# mcu.net
KiCad netlist of a schematic drawn in Altium Designer
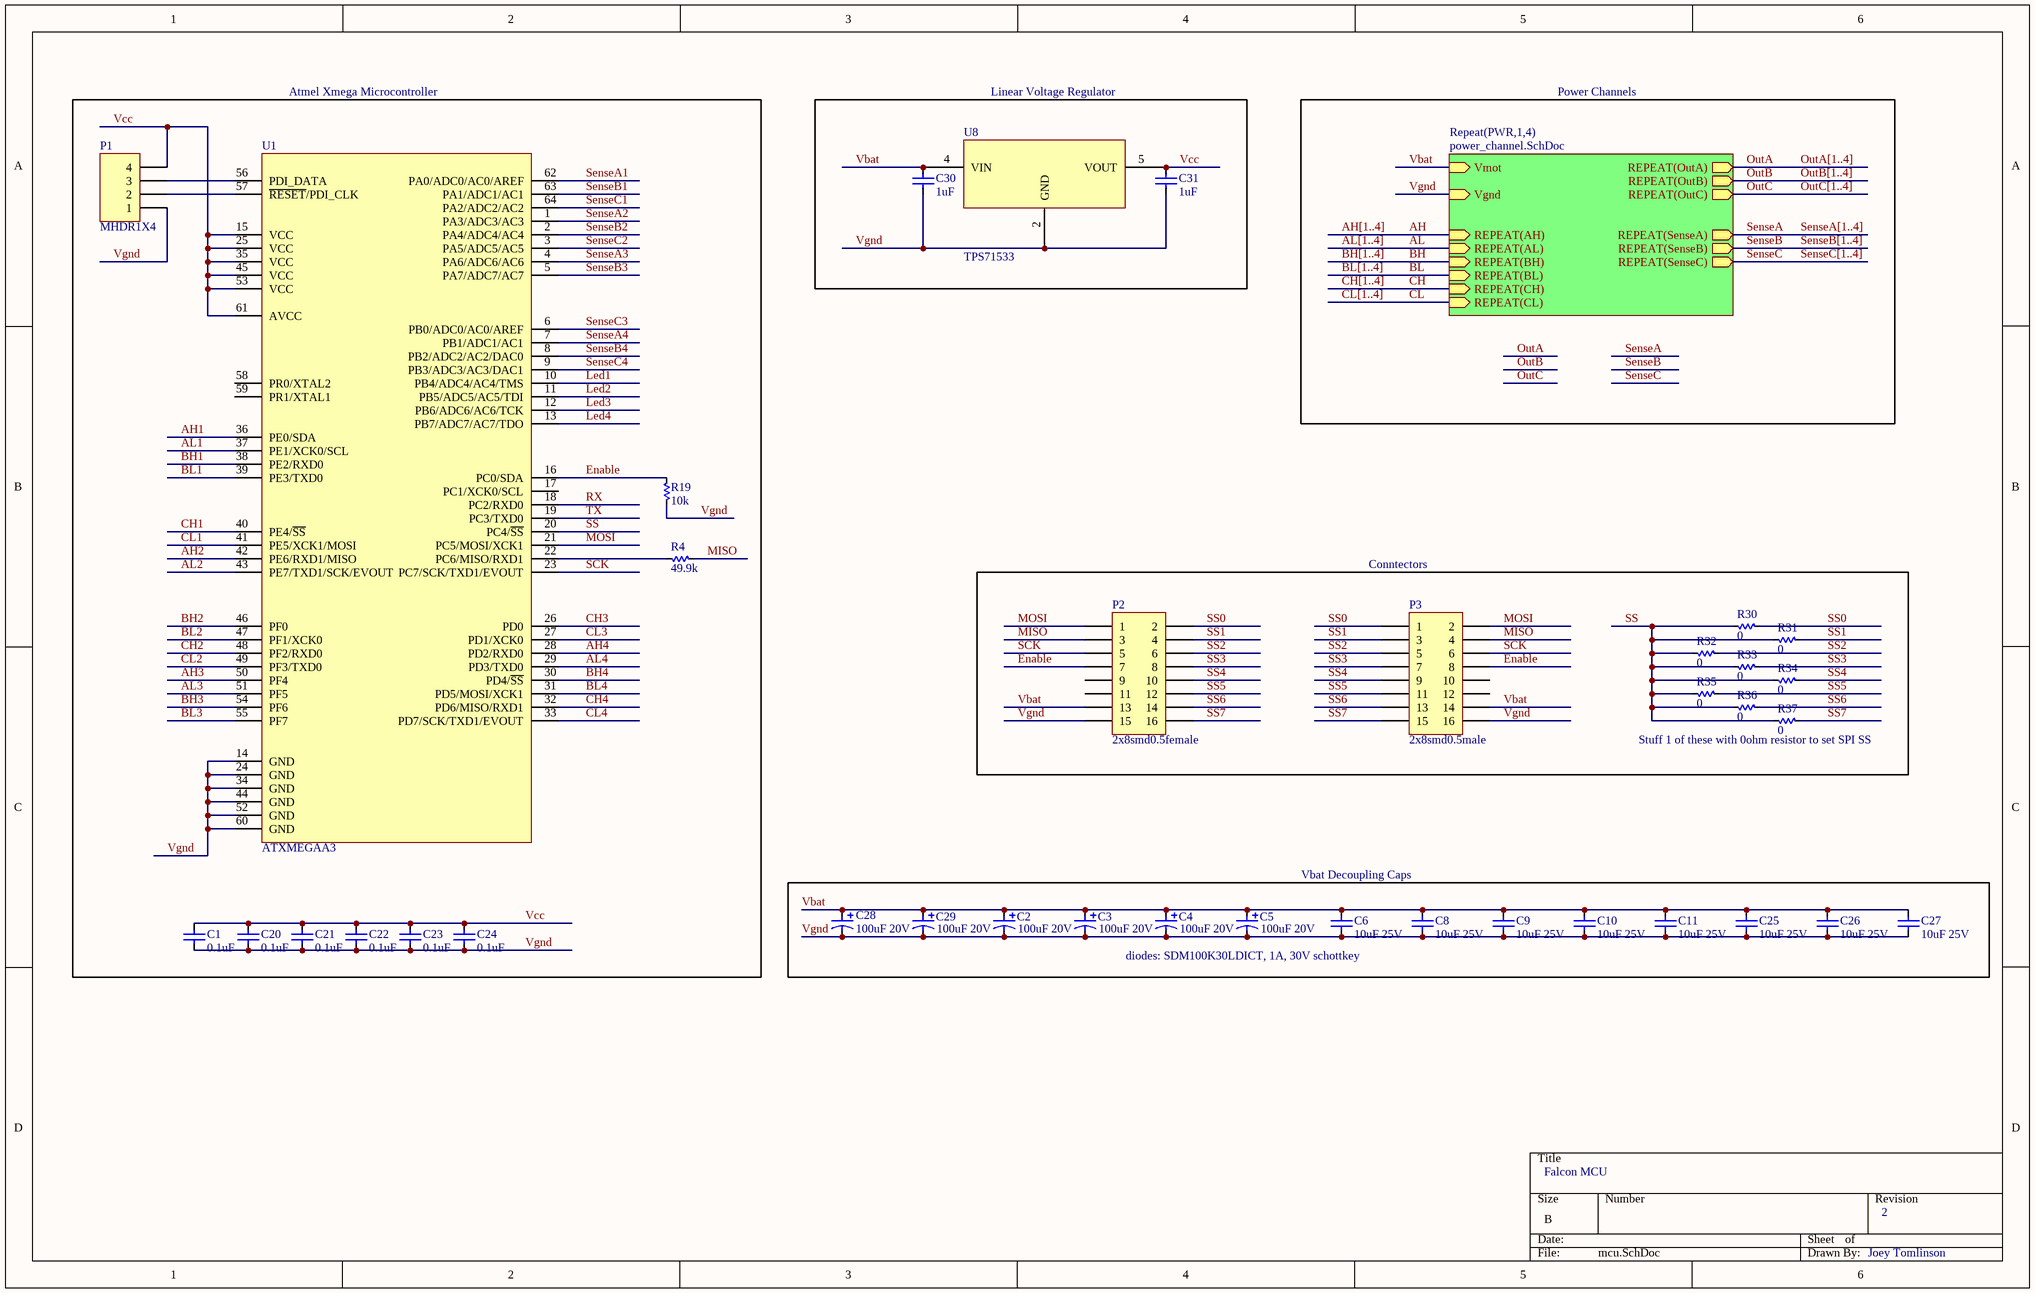
[diagram p0: mcu.SchDoc]

(export (version "E")
  (design (tool "Eeschema 10.0.6"))
  (components
    (comp (ref "C1")
      (value "0.1uF")
      (footprint "0603 (1608)")
      (fields (field (name "PART NO.") "490-1524-1-ND") (field (name "Comment") "Capacitor"))
      (libsource (lib "SMT Chip") (part "Capacitor"))
    )
    (comp (ref "C2")
      (value "100uF 20V")
      (footprint "7343 (TANT E)")
      (fields (field (name "PART NO.") "718-1370-1-ND") (field (name "Comment") "Polarized Capacitor"))
      (libsource (lib "SMT Chip") (part "Polarized Capacitor"))
    )
    (comp (ref "C3")
      (value "100uF 20V")
      (footprint "7343 (TANT E)")
      (fields (field (name "PART NO.") "718-1370-1-ND") (field (name "Comment") "Polarized Capacitor"))
      (libsource (lib "SMT Chip") (part "Polarized Capacitor"))
    )
    (comp (ref "C4")
      (value "100uF 20V")
      (footprint "7343 (TANT E)")
      (fields (field (name "PART NO.") "718-1370-1-ND") (field (name "Comment") "Polarized Capacitor"))
      (libsource (lib "SMT Chip") (part "Polarized Capacitor"))
    )
    (comp (ref "C5")
      (value "100uF 20V")
      (footprint "7343 (TANT E)")
      (fields (field (name "PART NO.") "718-1370-1-ND") (field (name "Comment") "Polarized Capacitor"))
      (libsource (lib "SMT Chip") (part "Polarized Capacitor"))
    )
    (comp (ref "C6")
      (value "10uF 25V")
      (footprint "0805 (2012)")
      (fields (field (name "PART NO.") "490-5523-1-ND") (field (name "Comment") "Capacitor"))
      (libsource (lib "SMT Chip") (part "Capacitor"))
    )
    (comp (ref "C8")
      (value "10uF 25V")
      (footprint "0805 (2012)")
      (fields (field (name "PART NO.") "490-5523-1-ND") (field (name "Comment") "Capacitor"))
      (libsource (lib "SMT Chip") (part "Capacitor"))
    )
    (comp (ref "C9")
      (value "10uF 25V")
      (footprint "0805 (2012)")
      (fields (field (name "PART NO.") "490-5523-1-ND") (field (name "Comment") "Capacitor"))
      (libsource (lib "SMT Chip") (part "Capacitor"))
    )
    (comp (ref "C10")
      (value "10uF 25V")
      (footprint "0805 (2012)")
      (fields (field (name "PART NO.") "490-5523-1-ND") (field (name "Comment") "Capacitor"))
      (libsource (lib "SMT Chip") (part "Capacitor"))
    )
    (comp (ref "C11")
      (value "10uF 25V")
      (footprint "0805 (2012)")
      (fields (field (name "PART NO.") "490-5523-1-ND") (field (name "Comment") "Capacitor"))
      (libsource (lib "SMT Chip") (part "Capacitor"))
    )
    (comp (ref "C20")
      (value "0.1uF")
      (footprint "0603 (1608)")
      (fields (field (name "PART NO.") "490-1524-1-ND") (field (name "Comment") "Capacitor"))
      (libsource (lib "SMT Chip") (part "Capacitor"))
    )
    (comp (ref "C21")
      (value "0.1uF")
      (footprint "0603 (1608)")
      (fields (field (name "PART NO.") "490-1524-1-ND") (field (name "Comment") "Capacitor"))
      (libsource (lib "SMT Chip") (part "Capacitor"))
    )
    (comp (ref "C22")
      (value "0.1uF")
      (footprint "0603 (1608)")
      (fields (field (name "PART NO.") "490-1524-1-ND") (field (name "Comment") "Capacitor"))
      (libsource (lib "SMT Chip") (part "Capacitor"))
    )
    (comp (ref "C23")
      (value "0.1uF")
      (footprint "0603 (1608)")
      (fields (field (name "PART NO.") "490-1524-1-ND") (field (name "Comment") "Capacitor"))
      (libsource (lib "SMT Chip") (part "Capacitor"))
    )
    (comp (ref "C24")
      (value "0.1uF")
      (footprint "0603 (1608)")
      (fields (field (name "PART NO.") "490-1524-1-ND") (field (name "Comment") "Capacitor"))
      (libsource (lib "SMT Chip") (part "Capacitor"))
    )
    (comp (ref "C25")
      (value "10uF 25V")
      (footprint "0805 (2012)")
      (fields (field (name "PART NO.") "490-5523-1-ND") (field (name "Comment") "Capacitor"))
      (libsource (lib "SMT Chip") (part "Capacitor"))
    )
    (comp (ref "C26")
      (value "10uF 25V")
      (footprint "0805 (2012)")
      (fields (field (name "PART NO.") "490-5523-1-ND") (field (name "Comment") "Capacitor"))
      (libsource (lib "SMT Chip") (part "Capacitor"))
    )
    (comp (ref "C27")
      (value "10uF 25V")
      (footprint "0805 (2012)")
      (fields (field (name "PART NO.") "490-5523-1-ND") (field (name "Comment") "Capacitor"))
      (libsource (lib "SMT Chip") (part "Capacitor"))
    )
    (comp (ref "C28")
      (value "100uF 20V")
      (footprint "7343 (TANT E)")
      (fields (field (name "PART NO.") "718-1370-1-ND") (field (name "Comment") "Polarized Capacitor"))
      (libsource (lib "SMT Chip") (part "Polarized Capacitor"))
    )
    (comp (ref "C29")
      (value "100uF 20V")
      (footprint "7343 (TANT E)")
      (fields (field (name "PART NO.") "718-1370-1-ND") (field (name "Comment") "Polarized Capacitor"))
      (libsource (lib "SMT Chip") (part "Polarized Capacitor"))
    )
    (comp (ref "C30")
      (value "1uF")
      (footprint "0603 (1608)")
      (fields (field (name "PART NO.") "445-3452-1-ND") (field (name "Comment") "Capacitor"))
      (libsource (lib "SMT Chip") (part "Capacitor"))
    )
    (comp (ref "C31")
      (value "1uF")
      (footprint "0603 (1608)")
      (fields (field (name "PART NO.") "445-3452-1-ND") (field (name "Comment") "Capacitor"))
      (libsource (lib "SMT Chip") (part "Capacitor"))
    )
    (comp (ref "P1")
      (value "MHDR1X4")
      (footprint "MHDR1X4")
      (description "Header, 4-Pin")
      (fields (field (name "PART NO.") "Not Stuffed") (field (name "PUBLISHER") "Altium Limited"))
      (libsource (lib "Miscellaneous Connectors") (part "MHDR1X4"))
    )
    (comp (ref "P2")
      (value "2x8smd0.5female")
      (footprint "S9007E-08-ND")
      (fields (field (name "PART NO.") "S9007E-08-ND"))
      (libsource (lib "falcon") (part "2x8smd0.5female"))
    )
    (comp (ref "P3")
      (value "2x8smd0.5male")
      (footprint "S9007E-08-ND")
      (fields (field (name "PART NO.") "S9013E-08-ND"))
      (libsource (lib "falcon") (part "2x8smd0.5male"))
    )
    (comp (ref "R4")
      (value "49.9k")
      (footprint "0603 (1608)")
      (description "Resistor")
      (fields (field (name "PART NO.") "P49.9HCT-ND"))
      (libsource (lib "SMT Chip") (part "Resistor"))
    )
    (comp (ref "R19")
      (value "10k")
      (footprint "0603 (1608)")
      (description "Resistor")
      (fields (field (name "PART NO.") "RMCF0603JT10K0CT-ND"))
      (libsource (lib "SMT Chip") (part "Resistor"))
    )
    (comp (ref "R30")
      (value "0")
      (footprint "0603 (1608)")
      (description "Resistor")
      (fields (field (name "PART NO.") "RMCF0603ZT0R00CT-ND"))
      (libsource (lib "SMT Chip") (part "Resistor"))
    )
    (comp (ref "R31")
      (value "0")
      (footprint "0603 (1608)")
      (description "Resistor")
      (fields (field (name "PART NO.") "RMCF0603ZT0R00CT-ND"))
      (libsource (lib "SMT Chip") (part "Resistor"))
    )
    (comp (ref "R32")
      (value "0")
      (footprint "0603 (1608)")
      (description "Resistor")
      (fields (field (name "PART NO.") "RMCF0603ZT0R00CT-ND"))
      (libsource (lib "SMT Chip") (part "Resistor"))
    )
    (comp (ref "R33")
      (value "0")
      (footprint "0603 (1608)")
      (description "Resistor")
      (fields (field (name "PART NO.") "RMCF0603ZT0R00CT-ND"))
      (libsource (lib "SMT Chip") (part "Resistor"))
    )
    (comp (ref "R34")
      (value "0")
      (footprint "0603 (1608)")
      (description "Resistor")
      (fields (field (name "PART NO.") "RMCF0603ZT0R00CT-ND"))
      (libsource (lib "SMT Chip") (part "Resistor"))
    )
    (comp (ref "R35")
      (value "0")
      (footprint "0603 (1608)")
      (description "Resistor")
      (fields (field (name "PART NO.") "RMCF0603ZT0R00CT-ND"))
      (libsource (lib "SMT Chip") (part "Resistor"))
    )
    (comp (ref "R36")
      (value "0")
      (footprint "0603 (1608)")
      (description "Resistor")
      (fields (field (name "PART NO.") "RMCF0603ZT0R00CT-ND"))
      (libsource (lib "SMT Chip") (part "Resistor"))
    )
    (comp (ref "R37")
      (value "0")
      (footprint "0603 (1608)")
      (description "Resistor")
      (fields (field (name "PART NO.") "RMCF0603ZT0R00CT-ND"))
      (libsource (lib "SMT Chip") (part "Resistor"))
    )
    (comp (ref "U1")
      (value "ATXMEGAA3")
      (footprint "QFN-64")
      (fields (field (name "MANUFACTURER") "Atmel") (field (name "PART NO.") "ATXMEGA128A3-MH-ND"))
      (libsource (lib "XMEGA") (part "ATXMEGAA3"))
    )
    (comp (ref "U8")
      (value "TPS71533")
      (footprint "SOT23-5")
      (fields (field (name "PART NO.") "296-12008-1-ND"))
      (libsource (lib "falcon") (part "TPS71533"))
    )
  )
  (nets
    (net (code "14") (name "/AH1") (class "Default")
      (node (ref "U1") (pin "36") (pinfunction "PE0/SDA_36") (pintype "passive"))
    )
    (net (code "15") (name "/AH2") (class "Default")
      (node (ref "U1") (pin "42") (pinfunction "PE6/RXD1/MISO_42") (pintype "passive"))
    )
    (net (code "16") (name "/AH3") (class "Default")
      (node (ref "U1") (pin "50") (pinfunction "PF4_50") (pintype "passive"))
    )
    (net (code "17") (name "/AH4") (class "Default")
      (node (ref "U1") (pin "28") (pinfunction "PD2/RXD0_28") (pintype "passive"))
    )
    (net (code "20") (name "/AL1") (class "Default")
      (node (ref "U1") (pin "37") (pinfunction "PE1/XCK0/SCL_37") (pintype "passive"))
    )
    (net (code "21") (name "/AL2") (class "Default")
      (node (ref "U1") (pin "43") (pinfunction "PE7/TXD1/SCK/EVOUT_43") (pintype "passive"))
    )
    (net (code "22") (name "/AL3") (class "Default")
      (node (ref "U1") (pin "51") (pinfunction "PF5_51") (pintype "passive"))
    )
    (net (code "23") (name "/AL4") (class "Default")
      (node (ref "U1") (pin "29") (pinfunction "PD3/TXD0_29") (pintype "passive"))
    )
    (net (code "26") (name "/BH1") (class "Default")
      (node (ref "U1") (pin "38") (pinfunction "PE2/RXD0_38") (pintype "passive"))
    )
    (net (code "27") (name "/BH2") (class "Default")
      (node (ref "U1") (pin "46") (pinfunction "PF0_46") (pintype "passive"))
    )
    (net (code "28") (name "/BH3") (class "Default")
      (node (ref "U1") (pin "54") (pinfunction "PF6_54") (pintype "passive"))
    )
    (net (code "29") (name "/BH4") (class "Default")
      (node (ref "U1") (pin "30") (pinfunction "PD4/~{SS}_30") (pintype "passive"))
    )
    (net (code "32") (name "/BL1") (class "Default")
      (node (ref "U1") (pin "39") (pinfunction "PE3/TXD0_39") (pintype "passive"))
    )
    (net (code "33") (name "/BL2") (class "Default")
      (node (ref "U1") (pin "47") (pinfunction "PF1/XCK0_47") (pintype "passive"))
    )
    (net (code "34") (name "/BL3") (class "Default")
      (node (ref "U1") (pin "55") (pinfunction "PF7_55") (pintype "passive"))
    )
    (net (code "35") (name "/BL4") (class "Default")
      (node (ref "U1") (pin "31") (pinfunction "PD5/MOSI/XCK1_31") (pintype "passive"))
    )
    (net (code "38") (name "/CH1") (class "Default")
      (node (ref "U1") (pin "40") (pinfunction "PE4/~{SS}_40") (pintype "passive"))
    )
    (net (code "39") (name "/CH2") (class "Default")
      (node (ref "U1") (pin "48") (pinfunction "PF2/RXD0_48") (pintype "passive"))
    )
    (net (code "40") (name "/CH3") (class "Default")
      (node (ref "U1") (pin "26") (pinfunction "PD0_26") (pintype "passive"))
    )
    (net (code "41") (name "/CH4") (class "Default")
      (node (ref "U1") (pin "32") (pinfunction "PD6/MISO/RXD1_32") (pintype "passive"))
    )
    (net (code "44") (name "/CL1") (class "Default")
      (node (ref "U1") (pin "41") (pinfunction "PE5/XCK1/MOSI_41") (pintype "passive"))
    )
    (net (code "45") (name "/CL2") (class "Default")
      (node (ref "U1") (pin "49") (pinfunction "PF3/TXD0_49") (pintype "passive"))
    )
    (net (code "46") (name "/CL3") (class "Default")
      (node (ref "U1") (pin "27") (pinfunction "PD1/XCK0_27") (pintype "passive"))
    )
    (net (code "47") (name "/CL4") (class "Default")
      (node (ref "U1") (pin "33") (pinfunction "PD7/SCK/TXD1/EVOUT_33") (pintype "passive"))
    )
    (net (code "49") (name "/Enable") (class "Default")
      (node (ref "P2") (pin "7") (pinfunction "7_7") (pintype "passive"))
      (node (ref "P3") (pin "8") (pinfunction "8_8") (pintype "passive"))
      (node (ref "R19") (pin "2") (pinfunction "2_2") (pintype "passive"))
      (node (ref "U1") (pin "16") (pinfunction "PC0/SDA_16") (pintype "passive"))
    )
    (net (code "50") (name "/Led1") (class "Default")
      (node (ref "U1") (pin "10") (pinfunction "PB4/ADC4/AC4/TMS_10") (pintype "passive"))
    )
    (net (code "51") (name "/Led2") (class "Default")
      (node (ref "U1") (pin "11") (pinfunction "PB5/ADC5/AC5/TDI_11") (pintype "passive"))
    )
    (net (code "52") (name "/Led3") (class "Default")
      (node (ref "U1") (pin "12") (pinfunction "PB6/ADC6/AC6/TCK_12") (pintype "passive"))
    )
    (net (code "53") (name "/Led4") (class "Default")
      (node (ref "U1") (pin "13") (pinfunction "PB7/ADC7/AC7/TDO_13") (pintype "passive"))
    )
    (net (code "54") (name "/MISO") (class "Default")
      (node (ref "P2") (pin "3") (pinfunction "3_3") (pintype "passive"))
      (node (ref "P3") (pin "4") (pinfunction "4_4") (pintype "passive"))
      (node (ref "R4") (pin "1") (pinfunction "1_1") (pintype "passive"))
    )
    (net (code "55") (name "/MOSI") (class "Default")
      (node (ref "P2") (pin "1") (pinfunction "1_1") (pintype "passive"))
      (node (ref "P3") (pin "2") (pinfunction "2_2") (pintype "passive"))
      (node (ref "U1") (pin "21") (pinfunction "PC5/MOSI/XCK1_21") (pintype "passive"))
    )
    (net (code "62") (name "/RX") (class "Default")
      (node (ref "U1") (pin "18") (pinfunction "PC2/RXD0_18") (pintype "passive"))
    )
    (net (code "63") (name "/SCK") (class "Default")
      (node (ref "P2") (pin "5") (pinfunction "5_5") (pintype "passive"))
      (node (ref "P3") (pin "6") (pinfunction "6_6") (pintype "passive"))
      (node (ref "U1") (pin "23") (pinfunction "PC7/SCK/TXD1/EVOUT_23") (pintype "passive"))
    )
    (net (code "64") (name "/SS") (class "Default")
      (node (ref "R30") (pin "1") (pinfunction "1_1") (pintype "passive"))
      (node (ref "R31") (pin "1") (pinfunction "1_1") (pintype "passive"))
      (node (ref "R32") (pin "1") (pinfunction "1_1") (pintype "passive"))
      (node (ref "R33") (pin "1") (pinfunction "1_1") (pintype "passive"))
      (node (ref "R34") (pin "1") (pinfunction "1_1") (pintype "passive"))
      (node (ref "R35") (pin "1") (pinfunction "1_1") (pintype "passive"))
      (node (ref "R36") (pin "1") (pinfunction "1_1") (pintype "passive"))
      (node (ref "R37") (pin "1") (pinfunction "1_1") (pintype "passive"))
      (node (ref "U1") (pin "20") (pinfunction "PC4/~{SS}_20") (pintype "passive"))
    )
    (net (code "65") (name "/SS0") (class "Default")
      (node (ref "P2") (pin "2") (pinfunction "2_2") (pintype "passive"))
      (node (ref "P3") (pin "1") (pinfunction "1_1") (pintype "passive"))
      (node (ref "R30") (pin "2") (pinfunction "2_2") (pintype "passive"))
    )
    (net (code "66") (name "/SS1") (class "Default")
      (node (ref "P2") (pin "4") (pinfunction "4_4") (pintype "passive"))
      (node (ref "P3") (pin "3") (pinfunction "3_3") (pintype "passive"))
      (node (ref "R31") (pin "2") (pinfunction "2_2") (pintype "passive"))
    )
    (net (code "67") (name "/SS2") (class "Default")
      (node (ref "P2") (pin "6") (pinfunction "6_6") (pintype "passive"))
      (node (ref "P3") (pin "5") (pinfunction "5_5") (pintype "passive"))
      (node (ref "R32") (pin "2") (pinfunction "2_2") (pintype "passive"))
    )
    (net (code "68") (name "/SS3") (class "Default")
      (node (ref "P2") (pin "8") (pinfunction "8_8") (pintype "passive"))
      (node (ref "P3") (pin "7") (pinfunction "7_7") (pintype "passive"))
      (node (ref "R33") (pin "2") (pinfunction "2_2") (pintype "passive"))
    )
    (net (code "69") (name "/SS4") (class "Default")
      (node (ref "P2") (pin "10") (pinfunction "10_10") (pintype "passive"))
      (node (ref "P3") (pin "9") (pinfunction "9_9") (pintype "passive"))
      (node (ref "R34") (pin "2") (pinfunction "2_2") (pintype "passive"))
    )
    (net (code "70") (name "/SS5") (class "Default")
      (node (ref "P2") (pin "12") (pinfunction "12_12") (pintype "passive"))
      (node (ref "P3") (pin "11") (pinfunction "11_11") (pintype "passive"))
      (node (ref "R35") (pin "2") (pinfunction "2_2") (pintype "passive"))
    )
    (net (code "71") (name "/SS6") (class "Default")
      (node (ref "P2") (pin "14") (pinfunction "14_14") (pintype "passive"))
      (node (ref "P3") (pin "13") (pinfunction "13_13") (pintype "passive"))
      (node (ref "R36") (pin "2") (pinfunction "2_2") (pintype "passive"))
    )
    (net (code "72") (name "/SS7") (class "Default")
      (node (ref "P2") (pin "16") (pinfunction "16_16") (pintype "passive"))
      (node (ref "P3") (pin "15") (pinfunction "15_15") (pintype "passive"))
      (node (ref "R37") (pin "2") (pinfunction "2_2") (pintype "passive"))
    )
    (net (code "74") (name "/SenseA1") (class "Default")
      (node (ref "U1") (pin "62") (pinfunction "PA0/ADC0/AC0/AREF_62") (pintype "passive"))
    )
    (net (code "75") (name "/SenseA2") (class "Default")
      (node (ref "U1") (pin "1") (pinfunction "PA3/ADC3/AC3_1") (pintype "passive"))
    )
    (net (code "76") (name "/SenseA3") (class "Default")
      (node (ref "U1") (pin "4") (pinfunction "PA6/ADC6/AC6_4") (pintype "passive"))
    )
    (net (code "77") (name "/SenseA4") (class "Default")
      (node (ref "U1") (pin "7") (pinfunction "PB1/ADC1/AC1_7") (pintype "passive"))
    )
    (net (code "80") (name "/SenseB1") (class "Default")
      (node (ref "U1") (pin "63") (pinfunction "PA1/ADC1/AC1_63") (pintype "passive"))
    )
    (net (code "81") (name "/SenseB2") (class "Default")
      (node (ref "U1") (pin "2") (pinfunction "PA4/ADC4/AC4_2") (pintype "passive"))
    )
    (net (code "82") (name "/SenseB3") (class "Default")
      (node (ref "U1") (pin "5") (pinfunction "PA7/ADC7/AC7_5") (pintype "passive"))
    )
    (net (code "83") (name "/SenseB4") (class "Default")
      (node (ref "U1") (pin "8") (pinfunction "PB2/ADC2/AC2/DAC0_8") (pintype "passive"))
    )
    (net (code "86") (name "/SenseC1") (class "Default")
      (node (ref "U1") (pin "64") (pinfunction "PA2/ADC2/AC2_64") (pintype "passive"))
    )
    (net (code "87") (name "/SenseC2") (class "Default")
      (node (ref "U1") (pin "3") (pinfunction "PA5/ADC5/AC5_3") (pintype "passive"))
    )
    (net (code "88") (name "/SenseC3") (class "Default")
      (node (ref "U1") (pin "6") (pinfunction "PB0/ADC0/AC0/AREF_6") (pintype "passive"))
    )
    (net (code "89") (name "/SenseC4") (class "Default")
      (node (ref "U1") (pin "9") (pinfunction "PB3/ADC3/AC3/DAC1_9") (pintype "passive"))
    )
    (net (code "91") (name "/TX") (class "Default")
      (node (ref "U1") (pin "19") (pinfunction "PC3/TXD0_19") (pintype "passive"))
    )
    (net (code "92") (name "/Vbat") (class "Default")
      (node (ref "C10") (pin "1") (pinfunction "1_1") (pintype "passive"))
      (node (ref "C11") (pin "1") (pinfunction "1_1") (pintype "passive"))
      (node (ref "C2") (pin "1") (pinfunction "1_1") (pintype "passive"))
      (node (ref "C25") (pin "1") (pinfunction "1_1") (pintype "passive"))
      (node (ref "C26") (pin "1") (pinfunction "1_1") (pintype "passive"))
      (node (ref "C27") (pin "1") (pinfunction "1_1") (pintype "passive"))
      (node (ref "C28") (pin "1") (pinfunction "1_1") (pintype "passive"))
      (node (ref "C29") (pin "1") (pinfunction "1_1") (pintype "passive"))
      (node (ref "C3") (pin "1") (pinfunction "1_1") (pintype "passive"))
      (node (ref "C30") (pin "1") (pinfunction "1_1") (pintype "passive"))
      (node (ref "C4") (pin "1") (pinfunction "1_1") (pintype "passive"))
      (node (ref "C5") (pin "1") (pinfunction "1_1") (pintype "passive"))
      (node (ref "C6") (pin "1") (pinfunction "1_1") (pintype "passive"))
      (node (ref "C8") (pin "1") (pinfunction "1_1") (pintype "passive"))
      (node (ref "C9") (pin "1") (pinfunction "1_1") (pintype "passive"))
      (node (ref "P2") (pin "13") (pinfunction "13_13") (pintype "passive"))
      (node (ref "P3") (pin "14") (pinfunction "14_14") (pintype "passive"))
      (node (ref "U8") (pin "4") (pinfunction "VIN_4") (pintype "passive"))
    )
    (net (code "93") (name "/Vcc") (class "Default")
      (node (ref "C1") (pin "1") (pinfunction "1_1") (pintype "passive"))
      (node (ref "C20") (pin "1") (pinfunction "1_1") (pintype "passive"))
      (node (ref "C21") (pin "1") (pinfunction "1_1") (pintype "passive"))
      (node (ref "C22") (pin "1") (pinfunction "1_1") (pintype "passive"))
      (node (ref "C23") (pin "1") (pinfunction "1_1") (pintype "passive"))
      (node (ref "C24") (pin "1") (pinfunction "1_1") (pintype "passive"))
      (node (ref "C31") (pin "1") (pinfunction "1_1") (pintype "passive"))
      (node (ref "P1") (pin "4") (pinfunction "4_4") (pintype "passive"))
      (node (ref "U1") (pin "15") (pinfunction "VCC_15") (pintype "passive"))
      (node (ref "U1") (pin "25") (pinfunction "VCC_25") (pintype "passive"))
      (node (ref "U1") (pin "35") (pinfunction "VCC_35") (pintype "passive"))
      (node (ref "U1") (pin "45") (pinfunction "VCC_45") (pintype "passive"))
      (node (ref "U1") (pin "53") (pinfunction "VCC_53") (pintype "passive"))
      (node (ref "U1") (pin "61") (pinfunction "AVCC_61") (pintype "passive"))
      (node (ref "U8") (pin "5") (pinfunction "VOUT_5") (pintype "passive"))
    )
    (net (code "94") (name "/Vgnd") (class "Default")
      (node (ref "C1") (pin "2") (pinfunction "2_2") (pintype "passive"))
      (node (ref "C10") (pin "2") (pinfunction "2_2") (pintype "passive"))
      (node (ref "C11") (pin "2") (pinfunction "2_2") (pintype "passive"))
      (node (ref "C2") (pin "2") (pinfunction "2_2") (pintype "passive"))
      (node (ref "C20") (pin "2") (pinfunction "2_2") (pintype "passive"))
      (node (ref "C21") (pin "2") (pinfunction "2_2") (pintype "passive"))
      (node (ref "C22") (pin "2") (pinfunction "2_2") (pintype "passive"))
      (node (ref "C23") (pin "2") (pinfunction "2_2") (pintype "passive"))
      (node (ref "C24") (pin "2") (pinfunction "2_2") (pintype "passive"))
      (node (ref "C25") (pin "2") (pinfunction "2_2") (pintype "passive"))
      (node (ref "C26") (pin "2") (pinfunction "2_2") (pintype "passive"))
      (node (ref "C27") (pin "2") (pinfunction "2_2") (pintype "passive"))
      (node (ref "C28") (pin "2") (pinfunction "2_2") (pintype "passive"))
      (node (ref "C29") (pin "2") (pinfunction "2_2") (pintype "passive"))
      (node (ref "C3") (pin "2") (pinfunction "2_2") (pintype "passive"))
      (node (ref "C30") (pin "2") (pinfunction "2_2") (pintype "passive"))
      (node (ref "C31") (pin "2") (pinfunction "2_2") (pintype "passive"))
      (node (ref "C4") (pin "2") (pinfunction "2_2") (pintype "passive"))
      (node (ref "C5") (pin "2") (pinfunction "2_2") (pintype "passive"))
      (node (ref "C6") (pin "2") (pinfunction "2_2") (pintype "passive"))
      (node (ref "C8") (pin "2") (pinfunction "2_2") (pintype "passive"))
      (node (ref "C9") (pin "2") (pinfunction "2_2") (pintype "passive"))
      (node (ref "P1") (pin "1") (pinfunction "1_1") (pintype "passive"))
      (node (ref "P2") (pin "15") (pinfunction "15_15") (pintype "passive"))
      (node (ref "P3") (pin "16") (pinfunction "16_16") (pintype "passive"))
      (node (ref "R19") (pin "1") (pinfunction "1_1") (pintype "passive"))
      (node (ref "U1") (pin "14") (pinfunction "GND_14") (pintype "passive"))
      (node (ref "U1") (pin "24") (pinfunction "GND_24") (pintype "passive"))
      (node (ref "U1") (pin "34") (pinfunction "GND_34") (pintype "passive"))
      (node (ref "U1") (pin "44") (pinfunction "GND_44") (pintype "passive"))
      (node (ref "U1") (pin "52") (pinfunction "GND_52") (pintype "passive"))
      (node (ref "U1") (pin "60") (pinfunction "GND_60") (pintype "passive"))
      (node (ref "U8") (pin "2") (pinfunction "GND_2") (pintype "passive"))
    )
    (net (code "95") (name "Net-(U1-PC6{slash}MISO{slash}RXD1)") (class "Default")
      (node (ref "R4") (pin "2") (pinfunction "2_2") (pintype "passive"))
      (node (ref "U1") (pin "22") (pinfunction "PC6/MISO/RXD1_22") (pintype "passive"))
    )
    (net (code "96") (name "Net-(U1-PDI_DATA)") (class "Default")
      (node (ref "P1") (pin "3") (pinfunction "3_3") (pintype "passive"))
      (node (ref "U1") (pin "56") (pinfunction "PDI_DATA_56") (pintype "passive"))
    )
    (net (code "97") (name "Net-(U1-~{RESET}{slash}PDI_CLK)") (class "Default")
      (node (ref "P1") (pin "2") (pinfunction "2_2") (pintype "passive"))
      (node (ref "U1") (pin "57") (pinfunction "~{RESET}/PDI_CLK_57") (pintype "passive"))
    )
    (net (code "98") (name "unconnected-(P2-Pad9)") (class "Default")
      (node (ref "P2") (pin "9") (pinfunction "9_9") (pintype "passive"))
    )
    (net (code "99") (name "unconnected-(P2-Pad11)") (class "Default")
      (node (ref "P2") (pin "11") (pinfunction "11_11") (pintype "passive"))
    )
    (net (code "100") (name "unconnected-(P3-Pad10)") (class "Default")
      (node (ref "P3") (pin "10") (pinfunction "10_10") (pintype "passive"))
    )
    (net (code "101") (name "unconnected-(P3-Pad12)") (class "Default")
      (node (ref "P3") (pin "12") (pinfunction "12_12") (pintype "passive"))
    )
    (net (code "102") (name "unconnected-(U1-PC1{slash}XCK0{slash}SCL-Pad17)") (class "Default")
      (node (ref "U1") (pin "17") (pinfunction "PC1/XCK0/SCL_17") (pintype "passive"))
    )
    (net (code "103") (name "unconnected-(U1-PR0{slash}XTAL2-Pad58)") (class "Default")
      (node (ref "U1") (pin "58") (pinfunction "PR0/XTAL2_58") (pintype "passive"))
    )
    (net (code "104") (name "unconnected-(U1-PR1{slash}XTAL1-Pad59)") (class "Default")
      (node (ref "U1") (pin "59") (pinfunction "PR1/XTAL1_59") (pintype "passive"))
    )
  )
)
